# pulse-generator.net
KiCad netlist of a schematic drawn in EAGLE
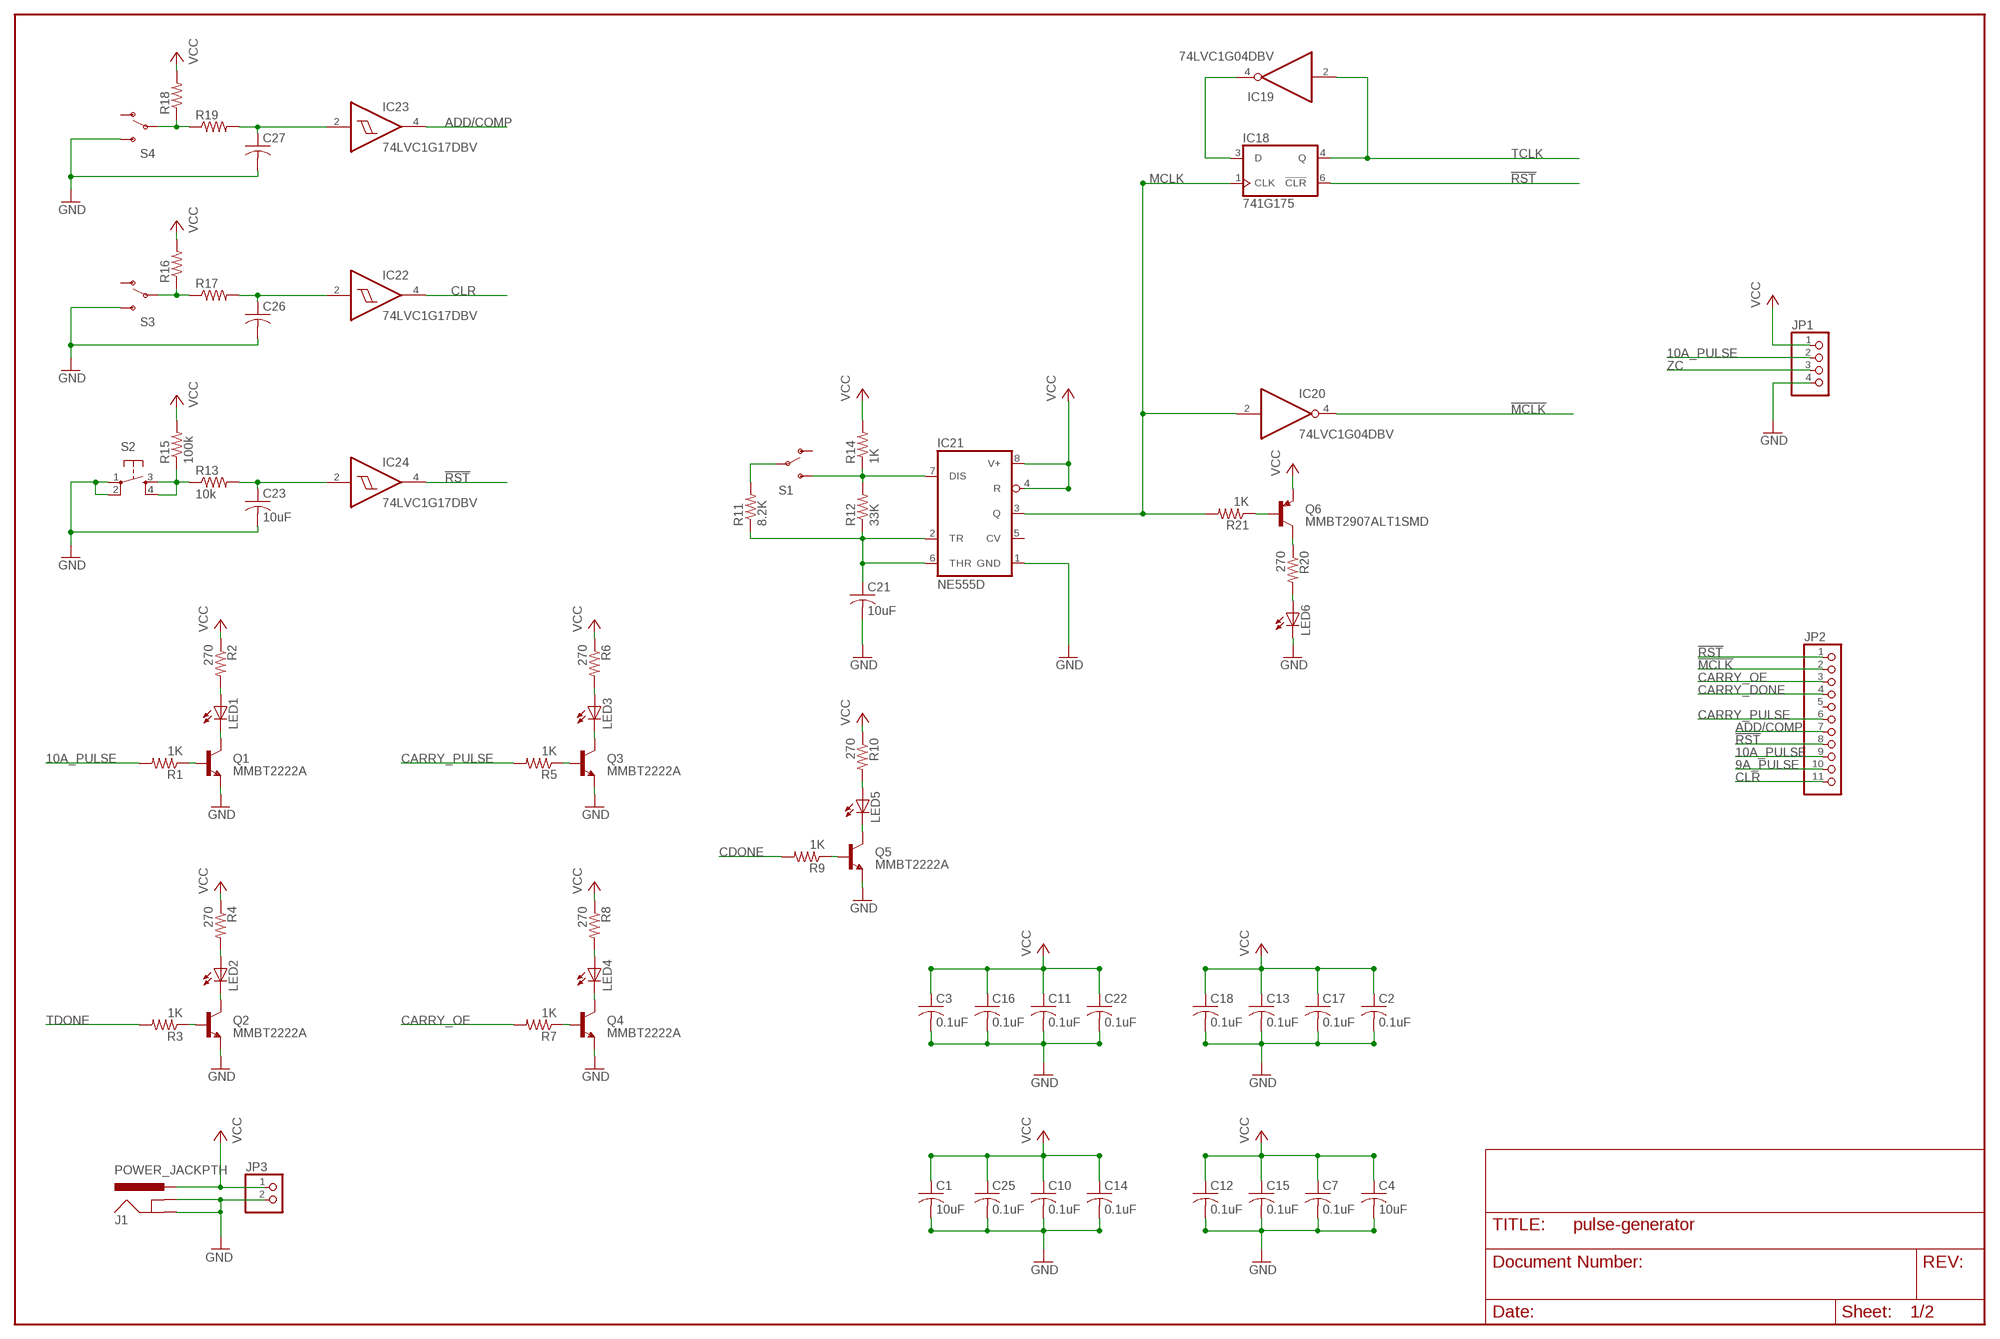
[diagram p0: schematic, sheet 1]
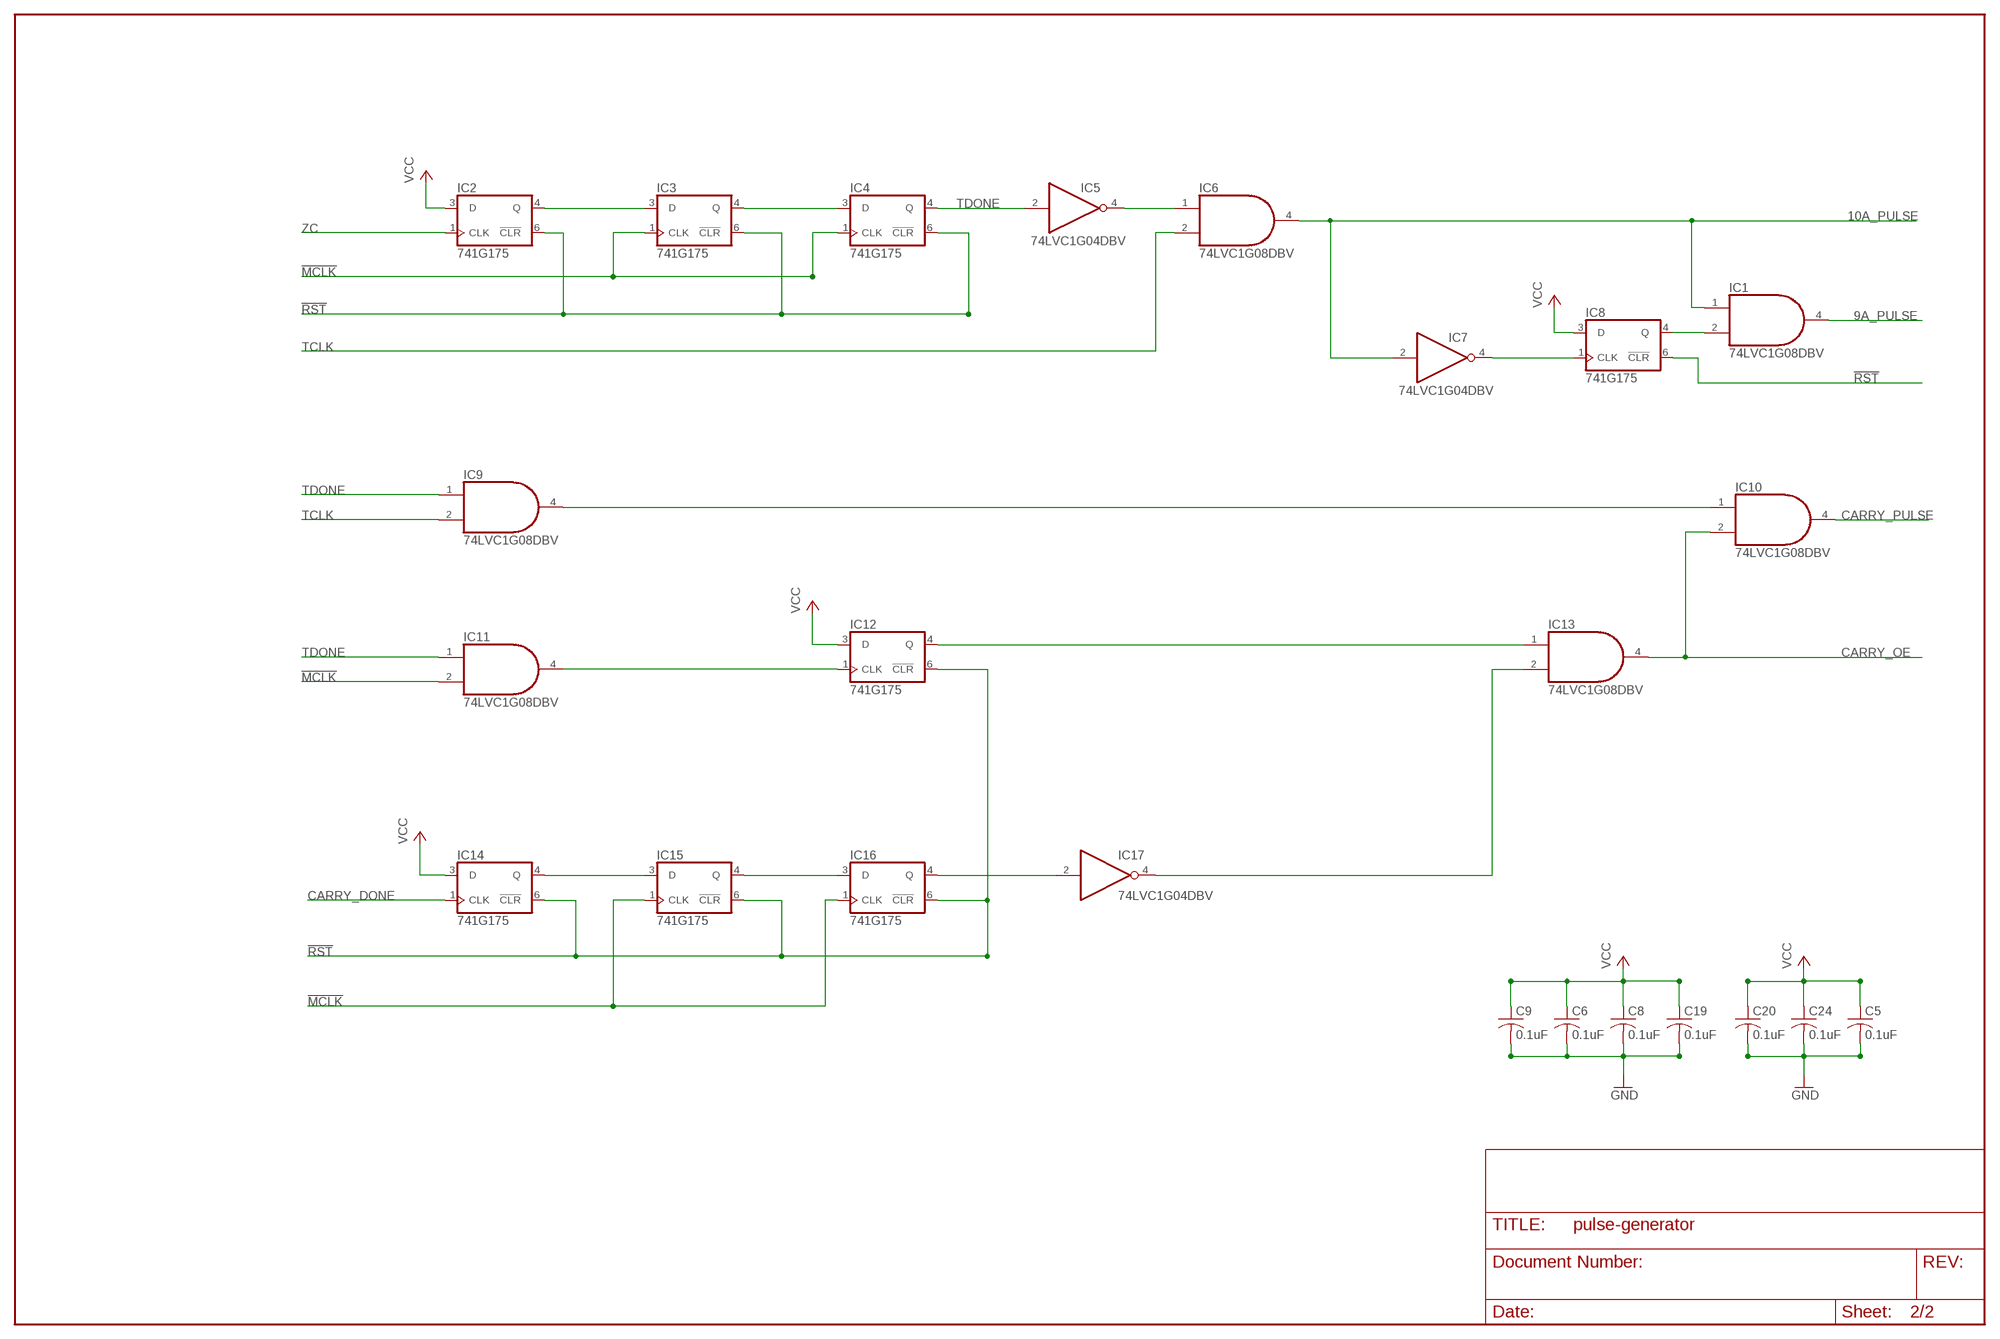
[diagram p1: schematic, sheet 2]

(export (version "E")
  (design (tool "Eeschema 10.0.6"))
  (components
    (comp (ref "C5")
      (value "0.1uF")
      (footprint "eagle-import:C0805")
      (libsource (lib "eagle-import") (part "C-USC0805"))
    )
    (comp (ref "C6")
      (value "0.1uF")
      (footprint "eagle-import:C0805")
      (libsource (lib "eagle-import") (part "C-USC0805"))
    )
    (comp (ref "C8")
      (value "0.1uF")
      (footprint "eagle-import:C0805")
      (libsource (lib "eagle-import") (part "C-USC0805"))
    )
    (comp (ref "C9")
      (value "0.1uF")
      (footprint "eagle-import:C0805")
      (libsource (lib "eagle-import") (part "C-USC0805"))
    )
    (comp (ref "C19")
      (value "0.1uF")
      (footprint "eagle-import:C0805")
      (libsource (lib "eagle-import") (part "C-USC0805"))
    )
    (comp (ref "C20")
      (value "0.1uF")
      (footprint "eagle-import:C0805")
      (libsource (lib "eagle-import") (part "C-USC0805"))
    )
    (comp (ref "C24")
      (value "0.1uF")
      (footprint "eagle-import:C0805")
      (libsource (lib "eagle-import") (part "C-USC0805"))
    )
    (comp (ref "IC1")
      (value "74LVC1G08DBV")
      (footprint "eagle-import:SOT23-5")
      (libsource (lib "eagle-import") (part "741G08DBVLVC"))
    )
    (comp (ref "IC2")
      (value "741G175")
      (footprint "eagle-import:DBV_R-PDSO-G6")
      (libsource (lib "eagle-import") (part "741G175"))
    )
    (comp (ref "IC3")
      (value "741G175")
      (footprint "eagle-import:DBV_R-PDSO-G6")
      (libsource (lib "eagle-import") (part "741G175"))
    )
    (comp (ref "IC4")
      (value "741G175")
      (footprint "eagle-import:DBV_R-PDSO-G6")
      (libsource (lib "eagle-import") (part "741G175"))
    )
    (comp (ref "IC5")
      (value "74LVC1G04DBV")
      (footprint "eagle-import:SOT23-5")
      (libsource (lib "eagle-import") (part "741G04DBVLVC"))
    )
    (comp (ref "IC6")
      (value "74LVC1G08DBV")
      (footprint "eagle-import:SOT23-5")
      (libsource (lib "eagle-import") (part "741G08DBVLVC"))
    )
    (comp (ref "IC7")
      (value "74LVC1G04DBV")
      (footprint "eagle-import:SOT23-5")
      (libsource (lib "eagle-import") (part "741G04DBVLVC"))
    )
    (comp (ref "IC8")
      (value "741G175")
      (footprint "eagle-import:DBV_R-PDSO-G6")
      (libsource (lib "eagle-import") (part "741G175"))
    )
    (comp (ref "IC9")
      (value "74LVC1G08DBV")
      (footprint "eagle-import:SOT23-5")
      (libsource (lib "eagle-import") (part "741G08DBVLVC"))
    )
    (comp (ref "IC10")
      (value "74LVC1G08DBV")
      (footprint "eagle-import:SOT23-5")
      (libsource (lib "eagle-import") (part "741G08DBVLVC"))
    )
    (comp (ref "IC11")
      (value "74LVC1G08DBV")
      (footprint "eagle-import:SOT23-5")
      (libsource (lib "eagle-import") (part "741G08DBVLVC"))
    )
    (comp (ref "IC12")
      (value "741G175")
      (footprint "eagle-import:DBV_R-PDSO-G6")
      (libsource (lib "eagle-import") (part "741G175"))
    )
    (comp (ref "IC13")
      (value "74LVC1G08DBV")
      (footprint "eagle-import:SOT23-5")
      (libsource (lib "eagle-import") (part "741G08DBVLVC"))
    )
    (comp (ref "IC14")
      (value "741G175")
      (footprint "eagle-import:DBV_R-PDSO-G6")
      (libsource (lib "eagle-import") (part "741G175"))
    )
    (comp (ref "IC15")
      (value "741G175")
      (footprint "eagle-import:DBV_R-PDSO-G6")
      (libsource (lib "eagle-import") (part "741G175"))
    )
    (comp (ref "IC16")
      (value "741G175")
      (footprint "eagle-import:DBV_R-PDSO-G6")
      (libsource (lib "eagle-import") (part "741G175"))
    )
    (comp (ref "IC17")
      (value "74LVC1G04DBV")
      (footprint "eagle-import:SOT23-5")
      (libsource (lib "eagle-import") (part "741G04DBVLVC"))
    )
    (comp (ref "C1")
      (value "10uF")
      (footprint "eagle-import:C0805")
      (libsource (lib "eagle-import") (part "C-USC0805"))
    )
    (comp (ref "C2")
      (value "0.1uF")
      (footprint "eagle-import:C0805")
      (libsource (lib "eagle-import") (part "C-USC0805"))
    )
    (comp (ref "C3")
      (value "0.1uF")
      (footprint "eagle-import:C0805")
      (libsource (lib "eagle-import") (part "C-USC0805"))
    )
    (comp (ref "C4")
      (value "10uF")
      (footprint "eagle-import:C0805")
      (libsource (lib "eagle-import") (part "C-USC0805"))
    )
    (comp (ref "C7")
      (value "0.1uF")
      (footprint "eagle-import:C0805")
      (libsource (lib "eagle-import") (part "C-USC0805"))
    )
    (comp (ref "C10")
      (value "0.1uF")
      (footprint "eagle-import:C0805")
      (libsource (lib "eagle-import") (part "C-USC0805"))
    )
    (comp (ref "C11")
      (value "0.1uF")
      (footprint "eagle-import:C0805")
      (libsource (lib "eagle-import") (part "C-USC0805"))
    )
    (comp (ref "C12")
      (value "0.1uF")
      (footprint "eagle-import:C0805")
      (libsource (lib "eagle-import") (part "C-USC0805"))
    )
    (comp (ref "C13")
      (value "0.1uF")
      (footprint "eagle-import:C0805")
      (libsource (lib "eagle-import") (part "C-USC0805"))
    )
    (comp (ref "C14")
      (value "0.1uF")
      (footprint "eagle-import:C0805")
      (libsource (lib "eagle-import") (part "C-USC0805"))
    )
    (comp (ref "C15")
      (value "0.1uF")
      (footprint "eagle-import:C0805")
      (libsource (lib "eagle-import") (part "C-USC0805"))
    )
    (comp (ref "C16")
      (value "0.1uF")
      (footprint "eagle-import:C0805")
      (libsource (lib "eagle-import") (part "C-USC0805"))
    )
    (comp (ref "C17")
      (value "0.1uF")
      (footprint "eagle-import:C0805")
      (libsource (lib "eagle-import") (part "C-USC0805"))
    )
    (comp (ref "C18")
      (value "0.1uF")
      (footprint "eagle-import:C0805")
      (libsource (lib "eagle-import") (part "C-USC0805"))
    )
    (comp (ref "C21")
      (value "10uF")
      (footprint "eagle-import:C0805")
      (libsource (lib "eagle-import") (part "C-USC0805"))
    )
    (comp (ref "C22")
      (value "0.1uF")
      (footprint "eagle-import:C0805")
      (libsource (lib "eagle-import") (part "C-USC0805"))
    )
    (comp (ref "C23")
      (value "10uF")
      (footprint "eagle-import:C0805")
      (libsource (lib "eagle-import") (part "C-USC0805"))
    )
    (comp (ref "C25")
      (value "0.1uF")
      (footprint "eagle-import:C0805")
      (libsource (lib "eagle-import") (part "C-USC0805"))
    )
    (comp (ref "C26")
      (value "C-USC0805")
      (footprint "eagle-import:C0805")
      (libsource (lib "eagle-import") (part "C-USC0805"))
    )
    (comp (ref "C27")
      (value "C-USC0805")
      (footprint "eagle-import:C0805")
      (libsource (lib "eagle-import") (part "C-USC0805"))
    )
    (comp (ref "IC18")
      (value "741G175")
      (footprint "eagle-import:DBV_R-PDSO-G6")
      (libsource (lib "eagle-import") (part "741G175"))
    )
    (comp (ref "IC19")
      (value "74LVC1G04DBV")
      (footprint "eagle-import:SOT23-5")
      (libsource (lib "eagle-import") (part "741G04DBVLVC"))
    )
    (comp (ref "IC20")
      (value "74LVC1G04DBV")
      (footprint "eagle-import:SOT23-5")
      (libsource (lib "eagle-import") (part "741G04DBVLVC"))
    )
    (comp (ref "IC21")
      (value "NE555D")
      (footprint "eagle-import:SO08")
      (libsource (lib "eagle-import") (part "555DNE"))
    )
    (comp (ref "IC22")
      (value "74LVC1G17DBV")
      (footprint "eagle-import:SOT23-5")
      (libsource (lib "eagle-import") (part "741G17DBVLVC"))
    )
    (comp (ref "IC23")
      (value "74LVC1G17DBV")
      (footprint "eagle-import:SOT23-5")
      (libsource (lib "eagle-import") (part "741G17DBVLVC"))
    )
    (comp (ref "IC24")
      (value "74LVC1G17DBV")
      (footprint "eagle-import:SOT23-5")
      (libsource (lib "eagle-import") (part "741G17DBVLVC"))
    )
    (comp (ref "J1")
      (value "POWER_JACKPTH")
      (footprint "eagle-import:POWER_JACK_PTH")
      (libsource (lib "eagle-import") (part "POWER_JACKPTH"))
    )
    (comp (ref "JP1")
      (value "PINHD-1X4")
      (footprint "eagle-import:1X04")
      (libsource (lib "eagle-import") (part "PINHD-1X4"))
    )
    (comp (ref "JP2")
      (value "PINHD-1X11")
      (footprint "eagle-import:1X11")
      (libsource (lib "eagle-import") (part "PINHD-1X11"))
    )
    (comp (ref "JP3")
      (value "PINHD-1X2")
      (footprint "eagle-import:1X02")
      (libsource (lib "eagle-import") (part "PINHD-1X2"))
    )
    (comp (ref "LED1")
      (value "LEDCHIP-LED0805")
      (footprint "eagle-import:CHIP-LED0805")
      (libsource (lib "eagle-import") (part "LEDCHIP-LED0805"))
    )
    (comp (ref "LED2")
      (value "LEDCHIP-LED0805")
      (footprint "eagle-import:CHIP-LED0805")
      (libsource (lib "eagle-import") (part "LEDCHIP-LED0805"))
    )
    (comp (ref "LED3")
      (value "LEDCHIP-LED0805")
      (footprint "eagle-import:CHIP-LED0805")
      (libsource (lib "eagle-import") (part "LEDCHIP-LED0805"))
    )
    (comp (ref "LED4")
      (value "LEDCHIP-LED0805")
      (footprint "eagle-import:CHIP-LED0805")
      (libsource (lib "eagle-import") (part "LEDCHIP-LED0805"))
    )
    (comp (ref "LED5")
      (value "LEDCHIP-LED0805")
      (footprint "eagle-import:CHIP-LED0805")
      (libsource (lib "eagle-import") (part "LEDCHIP-LED0805"))
    )
    (comp (ref "LED6")
      (value "LEDCHIP-LED0805")
      (footprint "eagle-import:CHIP-LED0805")
      (libsource (lib "eagle-import") (part "LEDCHIP-LED0805"))
    )
    (comp (ref "Q1")
      (value "MMBT2222A")
      (footprint "eagle-import:SOT23-3")
      (libsource (lib "eagle-import") (part "TRANSISTOR_NPNMMBT2222A"))
    )
    (comp (ref "Q2")
      (value "MMBT2222A")
      (footprint "eagle-import:SOT23-3")
      (libsource (lib "eagle-import") (part "TRANSISTOR_NPNMMBT2222A"))
    )
    (comp (ref "Q3")
      (value "MMBT2222A")
      (footprint "eagle-import:SOT23-3")
      (libsource (lib "eagle-import") (part "TRANSISTOR_NPNMMBT2222A"))
    )
    (comp (ref "Q4")
      (value "MMBT2222A")
      (footprint "eagle-import:SOT23-3")
      (libsource (lib "eagle-import") (part "TRANSISTOR_NPNMMBT2222A"))
    )
    (comp (ref "Q5")
      (value "MMBT2222A")
      (footprint "eagle-import:SOT23-3")
      (libsource (lib "eagle-import") (part "TRANSISTOR_NPNMMBT2222A"))
    )
    (comp (ref "Q6")
      (value "MMBT2907ALT1SMD")
      (footprint "eagle-import:SOT23-BEC")
      (libsource (lib "eagle-import") (part "MMBT2907SMDALT1"))
    )
    (comp (ref "R1")
      (value "1K")
      (footprint "eagle-import:R0805")
      (libsource (lib "eagle-import") (part "R-US_R0805"))
    )
    (comp (ref "R2")
      (value "270")
      (footprint "eagle-import:R0805")
      (libsource (lib "eagle-import") (part "R-US_R0805"))
    )
    (comp (ref "R3")
      (value "1K")
      (footprint "eagle-import:R0805")
      (libsource (lib "eagle-import") (part "R-US_R0805"))
    )
    (comp (ref "R4")
      (value "270")
      (footprint "eagle-import:R0805")
      (libsource (lib "eagle-import") (part "R-US_R0805"))
    )
    (comp (ref "R5")
      (value "1K")
      (footprint "eagle-import:R0805")
      (libsource (lib "eagle-import") (part "R-US_R0805"))
    )
    (comp (ref "R6")
      (value "270")
      (footprint "eagle-import:R0805")
      (libsource (lib "eagle-import") (part "R-US_R0805"))
    )
    (comp (ref "R7")
      (value "1K")
      (footprint "eagle-import:R0805")
      (libsource (lib "eagle-import") (part "R-US_R0805"))
    )
    (comp (ref "R8")
      (value "270")
      (footprint "eagle-import:R0805")
      (libsource (lib "eagle-import") (part "R-US_R0805"))
    )
    (comp (ref "R9")
      (value "1K")
      (footprint "eagle-import:R0805")
      (libsource (lib "eagle-import") (part "R-US_R0805"))
    )
    (comp (ref "R10")
      (value "270")
      (footprint "eagle-import:R0805")
      (libsource (lib "eagle-import") (part "R-US_R0805"))
    )
    (comp (ref "R11")
      (value "8.2K")
      (footprint "eagle-import:R0805")
      (libsource (lib "eagle-import") (part "R-US_R0805"))
    )
    (comp (ref "R12")
      (value "33K")
      (footprint "eagle-import:R0805")
      (libsource (lib "eagle-import") (part "R-US_R0805"))
    )
    (comp (ref "R13")
      (value "10k")
      (footprint "eagle-import:R0805")
      (libsource (lib "eagle-import") (part "R-US_R0805"))
    )
    (comp (ref "R14")
      (value "1K")
      (footprint "eagle-import:R0805")
      (libsource (lib "eagle-import") (part "R-US_R0805"))
    )
    (comp (ref "R15")
      (value "100k")
      (footprint "eagle-import:R0805")
      (libsource (lib "eagle-import") (part "R-US_R0805"))
    )
    (comp (ref "R16")
      (value "R-US_R0805")
      (footprint "eagle-import:R0805")
      (libsource (lib "eagle-import") (part "R-US_R0805"))
    )
    (comp (ref "R17")
      (value "R-US_R0805")
      (footprint "eagle-import:R0805")
      (libsource (lib "eagle-import") (part "R-US_R0805"))
    )
    (comp (ref "R18")
      (value "R-US_R0805")
      (footprint "eagle-import:R0805")
      (libsource (lib "eagle-import") (part "R-US_R0805"))
    )
    (comp (ref "R19")
      (value "R-US_R0805")
      (footprint "eagle-import:R0805")
      (libsource (lib "eagle-import") (part "R-US_R0805"))
    )
    (comp (ref "R20")
      (value "270")
      (footprint "eagle-import:R0805")
      (libsource (lib "eagle-import") (part "R-US_R0805"))
    )
    (comp (ref "R21")
      (value "1K")
      (footprint "eagle-import:R0805")
      (libsource (lib "eagle-import") (part "R-US_R0805"))
    )
    (comp (ref "S1")
      (value "SWITCH-SPDTPTH")
      (footprint "eagle-import:SWITCH-SPDT")
      (libsource (lib "eagle-import") (part "SWITCH-SPDTPTH"))
    )
    (comp (ref "S2")
      (value "TAC_SWITCHPTH")
      (footprint "eagle-import:TACTILE-PTH")
      (libsource (lib "eagle-import") (part "TAC_SWITCHPTH"))
    )
    (comp (ref "S3")
      (value "SWITCH-SPDTPTH")
      (footprint "eagle-import:SWITCH-SPDT")
      (libsource (lib "eagle-import") (part "SWITCH-SPDTPTH"))
    )
    (comp (ref "S4")
      (value "SWITCH-SPDTPTH")
      (footprint "eagle-import:SWITCH-SPDT")
      (libsource (lib "eagle-import") (part "SWITCH-SPDTPTH"))
    )
  )
  (nets
    (net (code "1") (name "9A_PULSE") (class "Default")
      (node (ref "IC1") (pin "4") (pinfunction "O_4") (pintype "output"))
      (node (ref "JP2") (pin "10") (pinfunction "10_10") (pintype "passive"))
    )
    (net (code "2") (name "10A_PULSE") (class "Default")
      (node (ref "IC1") (pin "1") (pinfunction "I0_1") (pintype "input"))
      (node (ref "IC6") (pin "4") (pinfunction "O_4") (pintype "output"))
      (node (ref "IC7") (pin "2") (pinfunction "I_2") (pintype "input"))
      (node (ref "JP1") (pin "2") (pinfunction "2_2") (pintype "passive"))
      (node (ref "JP2") (pin "9") (pinfunction "9_9") (pintype "passive"))
      (node (ref "R1") (pin "2") (pinfunction "2_2") (pintype "passive"))
    )
    (net (code "3") (name "ADD{slash}COMP") (class "Default")
      (node (ref "IC23") (pin "4") (pinfunction "O_4") (pintype "output"))
      (node (ref "JP2") (pin "7") (pinfunction "7_7") (pintype "passive"))
    )
    (net (code "4") (name "CARRY_DONE") (class "Default")
      (node (ref "IC14") (pin "1") (pinfunction "CLK_1") (pintype "input"))
      (node (ref "JP2") (pin "4") (pinfunction "4_4") (pintype "passive"))
    )
    (net (code "5") (name "CARRY_OE") (class "Default")
      (node (ref "IC10") (pin "2") (pinfunction "I1_2") (pintype "input"))
      (node (ref "IC13") (pin "4") (pinfunction "O_4") (pintype "output"))
      (node (ref "JP2") (pin "3") (pinfunction "3_3") (pintype "passive"))
      (node (ref "R7") (pin "2") (pinfunction "2_2") (pintype "passive"))
    )
    (net (code "6") (name "CARRY_PULSE") (class "Default")
      (node (ref "IC10") (pin "4") (pinfunction "O_4") (pintype "output"))
      (node (ref "JP2") (pin "6") (pinfunction "6_6") (pintype "passive"))
      (node (ref "R5") (pin "2") (pinfunction "2_2") (pintype "passive"))
    )
    (net (code "7") (name "CDONE") (class "Default")
      (node (ref "IC16") (pin "4") (pinfunction "Q_4") (pintype "output"))
      (node (ref "IC17") (pin "2") (pinfunction "I_2") (pintype "input"))
      (node (ref "R9") (pin "2") (pinfunction "2_2") (pintype "passive"))
    )
    (net (code "8") (name "CLR") (class "Default")
      (node (ref "IC22") (pin "4") (pinfunction "O_4") (pintype "output"))
      (node (ref "JP2") (pin "11") (pinfunction "11_11") (pintype "passive"))
    )
    (net (code "9") (name "GND") (class "Default")
      (node (ref "C1") (pin "2") (pinfunction "2_2") (pintype "passive"))
      (node (ref "C10") (pin "2") (pinfunction "2_2") (pintype "passive"))
      (node (ref "C11") (pin "2") (pinfunction "2_2") (pintype "passive"))
      (node (ref "C12") (pin "2") (pinfunction "2_2") (pintype "passive"))
      (node (ref "C13") (pin "2") (pinfunction "2_2") (pintype "passive"))
      (node (ref "C14") (pin "2") (pinfunction "2_2") (pintype "passive"))
      (node (ref "C15") (pin "2") (pinfunction "2_2") (pintype "passive"))
      (node (ref "C16") (pin "2") (pinfunction "2_2") (pintype "passive"))
      (node (ref "C17") (pin "2") (pinfunction "2_2") (pintype "passive"))
      (node (ref "C18") (pin "2") (pinfunction "2_2") (pintype "passive"))
      (node (ref "C19") (pin "2") (pinfunction "2_2") (pintype "passive"))
      (node (ref "C2") (pin "2") (pinfunction "2_2") (pintype "passive"))
      (node (ref "C20") (pin "2") (pinfunction "2_2") (pintype "passive"))
      (node (ref "C21") (pin "2") (pinfunction "2_2") (pintype "passive"))
      (node (ref "C22") (pin "2") (pinfunction "2_2") (pintype "passive"))
      (node (ref "C23") (pin "2") (pinfunction "2_2") (pintype "passive"))
      (node (ref "C24") (pin "2") (pinfunction "2_2") (pintype "passive"))
      (node (ref "C25") (pin "2") (pinfunction "2_2") (pintype "passive"))
      (node (ref "C26") (pin "2") (pinfunction "2_2") (pintype "passive"))
      (node (ref "C27") (pin "2") (pinfunction "2_2") (pintype "passive"))
      (node (ref "C3") (pin "2") (pinfunction "2_2") (pintype "passive"))
      (node (ref "C4") (pin "2") (pinfunction "2_2") (pintype "passive"))
      (node (ref "C5") (pin "2") (pinfunction "2_2") (pintype "passive"))
      (node (ref "C6") (pin "2") (pinfunction "2_2") (pintype "passive"))
      (node (ref "C7") (pin "2") (pinfunction "2_2") (pintype "passive"))
      (node (ref "C8") (pin "2") (pinfunction "2_2") (pintype "passive"))
      (node (ref "C9") (pin "2") (pinfunction "2_2") (pintype "passive"))
      (node (ref "IC21") (pin "1") (pinfunction "GND_1") (pintype "power_in"))
      (node (ref "J1") (pin "GND") (pinfunction "GND_GND") (pintype "bidirectional"))
      (node (ref "J1") (pin "GNDBREAK") (pinfunction "GNDBREAK_GNDBREAK") (pintype "bidirectional"))
      (node (ref "JP1") (pin "4") (pinfunction "4_4") (pintype "passive"))
      (node (ref "JP3") (pin "2") (pinfunction "2_2") (pintype "passive"))
      (node (ref "LED6") (pin "C") (pinfunction "C_C") (pintype "passive"))
      (node (ref "Q1") (pin "2") (pinfunction "E_2") (pintype "passive"))
      (node (ref "Q2") (pin "2") (pinfunction "E_2") (pintype "passive"))
      (node (ref "Q3") (pin "2") (pinfunction "E_2") (pintype "passive"))
      (node (ref "Q4") (pin "2") (pinfunction "E_2") (pintype "passive"))
      (node (ref "Q5") (pin "2") (pinfunction "E_2") (pintype "passive"))
      (node (ref "S2") (pin "1") (pinfunction "1_1") (pintype "passive"))
      (node (ref "S2") (pin "2") (pinfunction "2_2") (pintype "passive"))
      (node (ref "S3") (pin "3") (pinfunction "S_3") (pintype "passive"))
      (node (ref "S4") (pin "3") (pinfunction "S_3") (pintype "passive"))
    )
    (net (code "10") (name "MCLK") (class "Default")
      (node (ref "IC18") (pin "1") (pinfunction "CLK_1") (pintype "input"))
      (node (ref "IC20") (pin "2") (pinfunction "I_2") (pintype "input"))
      (node (ref "IC21") (pin "3") (pinfunction "Q_3") (pintype "output"))
      (node (ref "R21") (pin "2") (pinfunction "2_2") (pintype "passive"))
    )
    (net (code "11") (name "Net-(IC1A-I1)") (class "Default")
      (node (ref "IC1") (pin "2") (pinfunction "I1_2") (pintype "input"))
      (node (ref "IC8") (pin "4") (pinfunction "Q_4") (pintype "output"))
    )
    (net (code "12") (name "Net-(IC2A-Q)") (class "Default")
      (node (ref "IC2") (pin "4") (pinfunction "Q_4") (pintype "output"))
      (node (ref "IC3") (pin "3") (pinfunction "D_3") (pintype "input"))
    )
    (net (code "13") (name "Net-(IC3A-Q)") (class "Default")
      (node (ref "IC3") (pin "4") (pinfunction "Q_4") (pintype "output"))
      (node (ref "IC4") (pin "3") (pinfunction "D_3") (pintype "input"))
    )
    (net (code "14") (name "Net-(IC5A-O)") (class "Default")
      (node (ref "IC5") (pin "4") (pinfunction "O_4") (pintype "output"))
      (node (ref "IC6") (pin "1") (pinfunction "I0_1") (pintype "input"))
    )
    (net (code "15") (name "Net-(IC7A-O)") (class "Default")
      (node (ref "IC7") (pin "4") (pinfunction "O_4") (pintype "output"))
      (node (ref "IC8") (pin "1") (pinfunction "CLK_1") (pintype "input"))
    )
    (net (code "16") (name "Net-(IC10A-I0)") (class "Default")
      (node (ref "IC10") (pin "1") (pinfunction "I0_1") (pintype "input"))
      (node (ref "IC9") (pin "4") (pinfunction "O_4") (pintype "output"))
    )
    (net (code "17") (name "Net-(IC11A-O)") (class "Default")
      (node (ref "IC11") (pin "4") (pinfunction "O_4") (pintype "output"))
      (node (ref "IC12") (pin "1") (pinfunction "CLK_1") (pintype "input"))
    )
    (net (code "18") (name "Net-(IC12A-Q)") (class "Default")
      (node (ref "IC12") (pin "4") (pinfunction "Q_4") (pintype "output"))
      (node (ref "IC13") (pin "1") (pinfunction "I0_1") (pintype "input"))
    )
    (net (code "19") (name "Net-(IC13A-I1)") (class "Default")
      (node (ref "IC13") (pin "2") (pinfunction "I1_2") (pintype "input"))
      (node (ref "IC17") (pin "4") (pinfunction "O_4") (pintype "output"))
    )
    (net (code "20") (name "Net-(IC14A-Q)") (class "Default")
      (node (ref "IC14") (pin "4") (pinfunction "Q_4") (pintype "output"))
      (node (ref "IC15") (pin "3") (pinfunction "D_3") (pintype "input"))
    )
    (net (code "21") (name "Net-(IC15A-Q)") (class "Default")
      (node (ref "IC15") (pin "4") (pinfunction "Q_4") (pintype "output"))
      (node (ref "IC16") (pin "3") (pinfunction "D_3") (pintype "input"))
    )
    (net (code "22") (name "Net-(IC18A-D)") (class "Default")
      (node (ref "IC18") (pin "3") (pinfunction "D_3") (pintype "input"))
      (node (ref "IC19") (pin "4") (pinfunction "O_4") (pintype "output"))
    )
    (net (code "23") (name "Net-(IC21-DIS)") (class "Default")
      (node (ref "IC21") (pin "7") (pinfunction "DIS_7") (pintype "input"))
      (node (ref "R12") (pin "2") (pinfunction "2_2") (pintype "passive"))
      (node (ref "R14") (pin "1") (pinfunction "1_1") (pintype "passive"))
      (node (ref "S1") (pin "3") (pinfunction "S_3") (pintype "passive"))
    )
    (net (code "24") (name "Net-(IC21-THR)") (class "Default")
      (node (ref "C21") (pin "1") (pinfunction "1_1") (pintype "passive"))
      (node (ref "IC21") (pin "2") (pinfunction "TR_2") (pintype "input"))
      (node (ref "IC21") (pin "6") (pinfunction "THR_6") (pintype "input"))
      (node (ref "R11") (pin "1") (pinfunction "1_1") (pintype "passive"))
      (node (ref "R12") (pin "1") (pinfunction "1_1") (pintype "passive"))
    )
    (net (code "25") (name "Net-(IC22A-I)") (class "Default")
      (node (ref "C26") (pin "1") (pinfunction "1_1") (pintype "passive"))
      (node (ref "IC22") (pin "2") (pinfunction "I_2") (pintype "input"))
      (node (ref "R17") (pin "2") (pinfunction "2_2") (pintype "passive"))
    )
    (net (code "26") (name "Net-(IC23A-I)") (class "Default")
      (node (ref "C27") (pin "1") (pinfunction "1_1") (pintype "passive"))
      (node (ref "IC23") (pin "2") (pinfunction "I_2") (pintype "input"))
      (node (ref "R19") (pin "2") (pinfunction "2_2") (pintype "passive"))
    )
    (net (code "27") (name "Net-(IC24A-I)") (class "Default")
      (node (ref "C23") (pin "1") (pinfunction "1_1") (pintype "passive"))
      (node (ref "IC24") (pin "2") (pinfunction "I_2") (pintype "input"))
      (node (ref "R13") (pin "2") (pinfunction "2_2") (pintype "passive"))
    )
    (net (code "28") (name "Net-(LED1-PadA)") (class "Default")
      (node (ref "LED1") (pin "A") (pinfunction "A_A") (pintype "passive"))
      (node (ref "R2") (pin "2") (pinfunction "2_2") (pintype "passive"))
    )
    (net (code "29") (name "Net-(LED2-PadA)") (class "Default")
      (node (ref "LED2") (pin "A") (pinfunction "A_A") (pintype "passive"))
      (node (ref "R4") (pin "2") (pinfunction "2_2") (pintype "passive"))
    )
    (net (code "30") (name "Net-(LED3-PadA)") (class "Default")
      (node (ref "LED3") (pin "A") (pinfunction "A_A") (pintype "passive"))
      (node (ref "R6") (pin "2") (pinfunction "2_2") (pintype "passive"))
    )
    (net (code "31") (name "Net-(LED4-PadA)") (class "Default")
      (node (ref "LED4") (pin "A") (pinfunction "A_A") (pintype "passive"))
      (node (ref "R8") (pin "2") (pinfunction "2_2") (pintype "passive"))
    )
    (net (code "32") (name "Net-(LED5-PadA)") (class "Default")
      (node (ref "LED5") (pin "A") (pinfunction "A_A") (pintype "passive"))
      (node (ref "R10") (pin "2") (pinfunction "2_2") (pintype "passive"))
    )
    (net (code "33") (name "Net-(LED6-PadA)") (class "Default")
      (node (ref "LED6") (pin "A") (pinfunction "A_A") (pintype "passive"))
      (node (ref "R20") (pin "2") (pinfunction "2_2") (pintype "passive"))
    )
    (net (code "34") (name "Net-(Q1-B)") (class "Default")
      (node (ref "Q1") (pin "1") (pinfunction "B_1") (pintype "passive"))
      (node (ref "R1") (pin "1") (pinfunction "1_1") (pintype "passive"))
    )
    (net (code "35") (name "Net-(Q1-C)") (class "Default")
      (node (ref "LED1") (pin "C") (pinfunction "C_C") (pintype "passive"))
      (node (ref "Q1") (pin "3") (pinfunction "C_3") (pintype "passive"))
    )
    (net (code "36") (name "Net-(Q2-B)") (class "Default")
      (node (ref "Q2") (pin "1") (pinfunction "B_1") (pintype "passive"))
      (node (ref "R3") (pin "1") (pinfunction "1_1") (pintype "passive"))
    )
    (net (code "37") (name "Net-(Q2-C)") (class "Default")
      (node (ref "LED2") (pin "C") (pinfunction "C_C") (pintype "passive"))
      (node (ref "Q2") (pin "3") (pinfunction "C_3") (pintype "passive"))
    )
    (net (code "38") (name "Net-(Q3-B)") (class "Default")
      (node (ref "Q3") (pin "1") (pinfunction "B_1") (pintype "passive"))
      (node (ref "R5") (pin "1") (pinfunction "1_1") (pintype "passive"))
    )
    (net (code "39") (name "Net-(Q3-C)") (class "Default")
      (node (ref "LED3") (pin "C") (pinfunction "C_C") (pintype "passive"))
      (node (ref "Q3") (pin "3") (pinfunction "C_3") (pintype "passive"))
    )
    (net (code "40") (name "Net-(Q4-B)") (class "Default")
      (node (ref "Q4") (pin "1") (pinfunction "B_1") (pintype "passive"))
      (node (ref "R7") (pin "1") (pinfunction "1_1") (pintype "passive"))
    )
    (net (code "41") (name "Net-(Q4-C)") (class "Default")
      (node (ref "LED4") (pin "C") (pinfunction "C_C") (pintype "passive"))
      (node (ref "Q4") (pin "3") (pinfunction "C_3") (pintype "passive"))
    )
    (net (code "42") (name "Net-(Q5-B)") (class "Default")
      (node (ref "Q5") (pin "1") (pinfunction "B_1") (pintype "passive"))
      (node (ref "R9") (pin "1") (pinfunction "1_1") (pintype "passive"))
    )
    (net (code "43") (name "Net-(Q5-C)") (class "Default")
      (node (ref "LED5") (pin "C") (pinfunction "C_C") (pintype "passive"))
      (node (ref "Q5") (pin "3") (pinfunction "C_3") (pintype "passive"))
    )
    (net (code "44") (name "Net-(Q6-PadB)") (class "Default")
      (node (ref "Q6") (pin "B") (pinfunction "B_B") (pintype "passive"))
      (node (ref "R21") (pin "1") (pinfunction "1_1") (pintype "passive"))
    )
    (net (code "45") (name "Net-(Q6-PadC)") (class "Default")
      (node (ref "Q6") (pin "C") (pinfunction "C_C") (pintype "passive"))
      (node (ref "R20") (pin "1") (pinfunction "1_1") (pintype "passive"))
    )
    (net (code "46") (name "Net-(R13-Pad1)") (class "Default")
      (node (ref "R13") (pin "1") (pinfunction "1_1") (pintype "passive"))
      (node (ref "R15") (pin "1") (pinfunction "1_1") (pintype "passive"))
      (node (ref "S2") (pin "3") (pinfunction "3_3") (pintype "passive"))
      (node (ref "S2") (pin "4") (pinfunction "4_4") (pintype "passive"))
    )
    (net (code "47") (name "Net-(S1-P)") (class "Default")
      (node (ref "R11") (pin "2") (pinfunction "2_2") (pintype "passive"))
      (node (ref "S1") (pin "2") (pinfunction "P_2") (pintype "passive"))
    )
    (net (code "48") (name "Net-(S3-P)") (class "Default")
      (node (ref "R16") (pin "1") (pinfunction "1_1") (pintype "passive"))
      (node (ref "R17") (pin "1") (pinfunction "1_1") (pintype "passive"))
      (node (ref "S3") (pin "2") (pinfunction "P_2") (pintype "passive"))
    )
    (net (code "49") (name "Net-(S4-P)") (class "Default")
      (node (ref "R18") (pin "1") (pinfunction "1_1") (pintype "passive"))
      (node (ref "R19") (pin "1") (pinfunction "1_1") (pintype "passive"))
      (node (ref "S4") (pin "2") (pinfunction "P_2") (pintype "passive"))
    )
    (net (code "50") (name "TCLK") (class "Default")
      (node (ref "IC18") (pin "4") (pinfunction "Q_4") (pintype "output"))
      (node (ref "IC19") (pin "2") (pinfunction "I_2") (pintype "input"))
      (node (ref "IC6") (pin "2") (pinfunction "I1_2") (pintype "input"))
      (node (ref "IC9") (pin "2") (pinfunction "I1_2") (pintype "input"))
    )
    (net (code "51") (name "TDONE") (class "Default")
      (node (ref "IC11") (pin "1") (pinfunction "I0_1") (pintype "input"))
      (node (ref "IC4") (pin "4") (pinfunction "Q_4") (pintype "output"))
      (node (ref "IC5") (pin "2") (pinfunction "I_2") (pintype "input"))
      (node (ref "IC9") (pin "1") (pinfunction "I0_1") (pintype "input"))
      (node (ref "R3") (pin "2") (pinfunction "2_2") (pintype "passive"))
    )
    (net (code "52") (name "VCC") (class "Default")
      (node (ref "C1") (pin "1") (pinfunction "1_1") (pintype "passive"))
      (node (ref "C10") (pin "1") (pinfunction "1_1") (pintype "passive"))
      (node (ref "C11") (pin "1") (pinfunction "1_1") (pintype "passive"))
      (node (ref "C12") (pin "1") (pinfunction "1_1") (pintype "passive"))
      (node (ref "C13") (pin "1") (pinfunction "1_1") (pintype "passive"))
      (node (ref "C14") (pin "1") (pinfunction "1_1") (pintype "passive"))
      (node (ref "C15") (pin "1") (pinfunction "1_1") (pintype "passive"))
      (node (ref "C16") (pin "1") (pinfunction "1_1") (pintype "passive"))
      (node (ref "C17") (pin "1") (pinfunction "1_1") (pintype "passive"))
      (node (ref "C18") (pin "1") (pinfunction "1_1") (pintype "passive"))
      (node (ref "C19") (pin "1") (pinfunction "1_1") (pintype "passive"))
      (node (ref "C2") (pin "1") (pinfunction "1_1") (pintype "passive"))
      (node (ref "C20") (pin "1") (pinfunction "1_1") (pintype "passive"))
      (node (ref "C22") (pin "1") (pinfunction "1_1") (pintype "passive"))
      (node (ref "C24") (pin "1") (pinfunction "1_1") (pintype "passive"))
      (node (ref "C25") (pin "1") (pinfunction "1_1") (pintype "passive"))
      (node (ref "C3") (pin "1") (pinfunction "1_1") (pintype "passive"))
      (node (ref "C4") (pin "1") (pinfunction "1_1") (pintype "passive"))
      (node (ref "C5") (pin "1") (pinfunction "1_1") (pintype "passive"))
      (node (ref "C6") (pin "1") (pinfunction "1_1") (pintype "passive"))
      (node (ref "C7") (pin "1") (pinfunction "1_1") (pintype "passive"))
      (node (ref "C8") (pin "1") (pinfunction "1_1") (pintype "passive"))
      (node (ref "C9") (pin "1") (pinfunction "1_1") (pintype "passive"))
      (node (ref "IC12") (pin "3") (pinfunction "D_3") (pintype "input"))
      (node (ref "IC14") (pin "3") (pinfunction "D_3") (pintype "input"))
      (node (ref "IC2") (pin "3") (pinfunction "D_3") (pintype "input"))
      (node (ref "IC21") (pin "4") (pinfunction "R_4") (pintype "input"))
      (node (ref "IC21") (pin "8") (pinfunction "V+_8") (pintype "power_in"))
      (node (ref "IC8") (pin "3") (pinfunction "D_3") (pintype "input"))
      (node (ref "J1") (pin "PWR") (pinfunction "PWR_PWR") (pintype "bidirectional"))
      (node (ref "JP1") (pin "1") (pinfunction "1_1") (pintype "passive"))
      (node (ref "JP3") (pin "1") (pinfunction "1_1") (pintype "passive"))
      (node (ref "Q6") (pin "E") (pinfunction "E_E") (pintype "passive"))
      (node (ref "R10") (pin "1") (pinfunction "1_1") (pintype "passive"))
      (node (ref "R14") (pin "2") (pinfunction "2_2") (pintype "passive"))
      (node (ref "R15") (pin "2") (pinfunction "2_2") (pintype "passive"))
      (node (ref "R16") (pin "2") (pinfunction "2_2") (pintype "passive"))
      (node (ref "R18") (pin "2") (pinfunction "2_2") (pintype "passive"))
      (node (ref "R2") (pin "1") (pinfunction "1_1") (pintype "passive"))
      (node (ref "R4") (pin "1") (pinfunction "1_1") (pintype "passive"))
      (node (ref "R6") (pin "1") (pinfunction "1_1") (pintype "passive"))
      (node (ref "R8") (pin "1") (pinfunction "1_1") (pintype "passive"))
    )
    (net (code "53") (name "ZC") (class "Default")
      (node (ref "IC2") (pin "1") (pinfunction "CLK_1") (pintype "input"))
      (node (ref "JP1") (pin "3") (pinfunction "3_3") (pintype "passive"))
    )
    (net (code "54") (name "unconnected-(IC21-CV-Pad5)") (class "Default")
      (node (ref "IC21") (pin "5") (pinfunction "CV_5") (pintype "input"))
    )
    (net (code "55") (name "unconnected-(JP2-Pad5)") (class "Default")
      (node (ref "JP2") (pin "5") (pinfunction "5_5") (pintype "passive"))
    )
    (net (code "56") (name "unconnected-(S1-O-Pad1)") (class "Default")
      (node (ref "S1") (pin "1") (pinfunction "O_1") (pintype "passive"))
    )
    (net (code "57") (name "unconnected-(S3-O-Pad1)") (class "Default")
      (node (ref "S3") (pin "1") (pinfunction "O_1") (pintype "passive"))
    )
    (net (code "58") (name "unconnected-(S4-O-Pad1)") (class "Default")
      (node (ref "S4") (pin "1") (pinfunction "O_1") (pintype "passive"))
    )
    (net (code "59") (name "~{MCLK}") (class "Default")
      (node (ref "IC11") (pin "2") (pinfunction "I1_2") (pintype "input"))
      (node (ref "IC15") (pin "1") (pinfunction "CLK_1") (pintype "input"))
      (node (ref "IC16") (pin "1") (pinfunction "CLK_1") (pintype "input"))
      (node (ref "IC20") (pin "4") (pinfunction "O_4") (pintype "output"))
      (node (ref "IC3") (pin "1") (pinfunction "CLK_1") (pintype "input"))
      (node (ref "IC4") (pin "1") (pinfunction "CLK_1") (pintype "input"))
      (node (ref "JP2") (pin "2") (pinfunction "2_2") (pintype "passive"))
    )
    (net (code "60") (name "~{RST}") (class "Default")
      (node (ref "IC12") (pin "6") (pinfunction "~{CLR}_6") (pintype "input"))
      (node (ref "IC14") (pin "6") (pinfunction "~{CLR}_6") (pintype "input"))
      (node (ref "IC15") (pin "6") (pinfunction "~{CLR}_6") (pintype "input"))
      (node (ref "IC16") (pin "6") (pinfunction "~{CLR}_6") (pintype "input"))
      (node (ref "IC18") (pin "6") (pinfunction "~{CLR}_6") (pintype "input"))
      (node (ref "IC2") (pin "6") (pinfunction "~{CLR}_6") (pintype "input"))
      (node (ref "IC24") (pin "4") (pinfunction "O_4") (pintype "output"))
      (node (ref "IC3") (pin "6") (pinfunction "~{CLR}_6") (pintype "input"))
      (node (ref "IC4") (pin "6") (pinfunction "~{CLR}_6") (pintype "input"))
      (node (ref "IC8") (pin "6") (pinfunction "~{CLR}_6") (pintype "input"))
      (node (ref "JP2") (pin "1") (pinfunction "1_1") (pintype "passive"))
      (node (ref "JP2") (pin "8") (pinfunction "8_8") (pintype "passive"))
    )
  )
)
